# robot.net
KiCad netlist of a schematic drawn in EAGLE
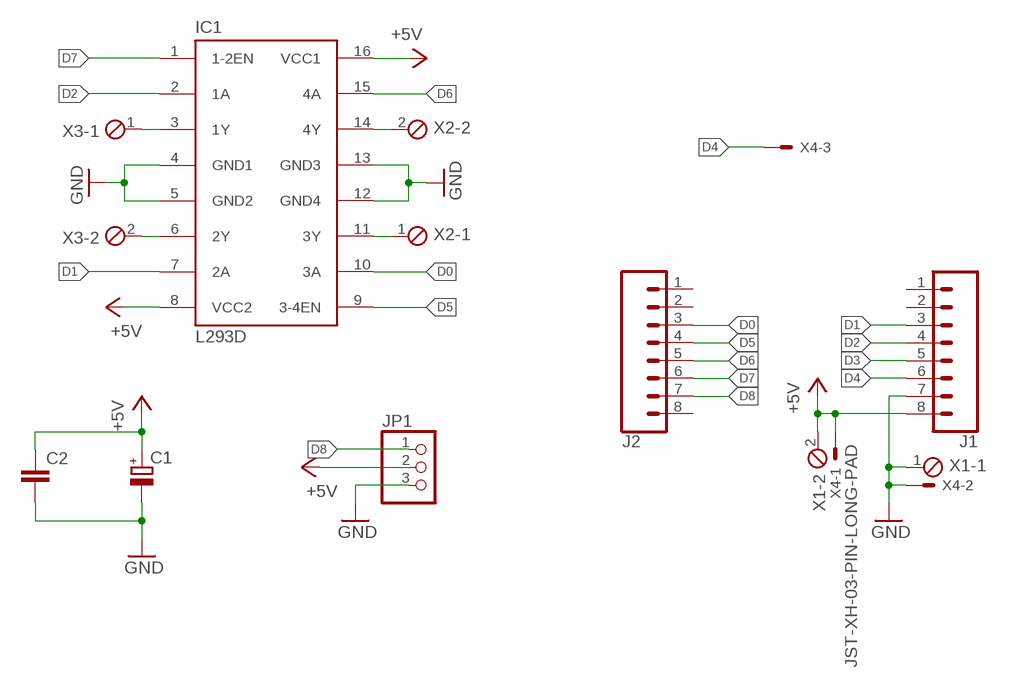
[diagram p0: schematic, sheet 1]

(export (version "E")
  (design (tool "Eeschema 10.0.6"))
  (components
    (comp (ref "C1")
      (value "CPOL-EUE2.5-7")
      (footprint "eagle-import:E2,5-7")
      (libsource (lib "eagle-import") (part "CPOL-EUE2.5-7"))
    )
    (comp (ref "C2")
      (value "C-EUC0805K")
      (footprint "eagle-import:C0805K")
      (libsource (lib "eagle-import") (part "C-EUC0805K"))
    )
    (comp (ref "IC1")
      (value "L293D")
      (footprint "eagle-import:DIL16")
      (libsource (lib "eagle-import") (part "L293D"))
    )
    (comp (ref "J1")
      (value "CONN_08\"")
      (footprint "eagle-import:1X08")
      (libsource (lib "eagle-import") (part "CONN_08{dblquote}"))
    )
    (comp (ref "J2")
      (value "CONN_08\"")
      (footprint "eagle-import:1X08")
      (libsource (lib "eagle-import") (part "CONN_08{dblquote}"))
    )
    (comp (ref "JP1")
      (value "PINHD-1X3")
      (footprint "eagle-import:1X03")
      (libsource (lib "eagle-import") (part "PINHD-1X3"))
    )
    (comp (ref "X1")
      (value "MPT2")
      (footprint "eagle-import:2POL254")
      (libsource (lib "eagle-import") (part "MPT2"))
    )
    (comp (ref "X2")
      (value "MPT2")
      (footprint "eagle-import:2POL254")
      (libsource (lib "eagle-import") (part "MPT2"))
    )
    (comp (ref "X3")
      (value "MPT2")
      (footprint "eagle-import:2POL254")
      (libsource (lib "eagle-import") (part "MPT2"))
    )
    (comp (ref "X4")
      (value "JST-XH-03-PIN-LONG-PAD")
      (footprint "eagle-import:JST-XH-03-PACKAGE-LONG-PAD")
      (libsource (lib "eagle-import") (part "JST-XH-03-PIN-LONG-PAD"))
    )
  )
  (nets
    (net (code "1") (name "+5V") (class "Default")
      (node (ref "C1") (pin "+") (pinfunction "+_+") (pintype "passive"))
      (node (ref "C2") (pin "1") (pinfunction "1_1") (pintype "passive"))
      (node (ref "IC1") (pin "16") (pinfunction "VCC1_16") (pintype "power_in"))
      (node (ref "IC1") (pin "8") (pinfunction "VCC2_8") (pintype "power_in"))
      (node (ref "J1") (pin "8") (pinfunction "8_8") (pintype "passive"))
      (node (ref "JP1") (pin "2") (pinfunction "2_2") (pintype "passive"))
      (node (ref "X1") (pin "2") (pinfunction "1_2") (pintype "passive"))
      (node (ref "X4") (pin "1") (pinfunction "S_1") (pintype "passive"))
    )
    (net (code "2") (name "D0") (class "Default")
      (node (ref "IC1") (pin "10") (pinfunction "3A_10") (pintype "input"))
      (node (ref "J2") (pin "3") (pinfunction "3_3") (pintype "passive"))
    )
    (net (code "3") (name "D1") (class "Default")
      (node (ref "IC1") (pin "7") (pinfunction "2A_7") (pintype "input"))
      (node (ref "J1") (pin "3") (pinfunction "3_3") (pintype "passive"))
    )
    (net (code "4") (name "D2") (class "Default")
      (node (ref "IC1") (pin "2") (pinfunction "1A_2") (pintype "input"))
      (node (ref "J1") (pin "4") (pinfunction "4_4") (pintype "passive"))
    )
    (net (code "5") (name "D3") (class "Default")
      (node (ref "J1") (pin "5") (pinfunction "5_5") (pintype "passive"))
    )
    (net (code "6") (name "D4") (class "Default")
      (node (ref "J1") (pin "6") (pinfunction "6_6") (pintype "passive"))
      (node (ref "X4") (pin "3") (pinfunction "S_3") (pintype "passive"))
    )
    (net (code "7") (name "D5") (class "Default")
      (node (ref "IC1") (pin "9") (pinfunction "3-4EN_9") (pintype "input"))
      (node (ref "J2") (pin "4") (pinfunction "4_4") (pintype "passive"))
    )
    (net (code "8") (name "D6") (class "Default")
      (node (ref "IC1") (pin "15") (pinfunction "4A_15") (pintype "input"))
      (node (ref "J2") (pin "5") (pinfunction "5_5") (pintype "passive"))
    )
    (net (code "9") (name "D7") (class "Default")
      (node (ref "IC1") (pin "1") (pinfunction "1-2EN_1") (pintype "input"))
      (node (ref "J2") (pin "6") (pinfunction "6_6") (pintype "passive"))
    )
    (net (code "10") (name "D8") (class "Default")
      (node (ref "J2") (pin "7") (pinfunction "7_7") (pintype "passive"))
      (node (ref "JP1") (pin "1") (pinfunction "1_1") (pintype "passive"))
    )
    (net (code "11") (name "GND") (class "Default")
      (node (ref "C1") (pin "-") (pinfunction "-_-") (pintype "passive"))
      (node (ref "C2") (pin "2") (pinfunction "2_2") (pintype "passive"))
      (node (ref "IC1") (pin "12") (pinfunction "GND4_12") (pintype "power_in"))
      (node (ref "IC1") (pin "13") (pinfunction "GND3_13") (pintype "power_in"))
      (node (ref "IC1") (pin "4") (pinfunction "GND1_4") (pintype "power_in"))
      (node (ref "IC1") (pin "5") (pinfunction "GND2_5") (pintype "power_in"))
      (node (ref "J1") (pin "7") (pinfunction "7_7") (pintype "passive"))
      (node (ref "JP1") (pin "3") (pinfunction "3_3") (pintype "passive"))
      (node (ref "X1") (pin "1") (pinfunction "1_1") (pintype "passive"))
      (node (ref "X4") (pin "2") (pinfunction "S_2") (pintype "passive"))
    )
    (net (code "12") (name "Net-(IC1-1Y)") (class "Default")
      (node (ref "IC1") (pin "3") (pinfunction "1Y_3") (pintype "output"))
      (node (ref "X3") (pin "1") (pinfunction "1_1") (pintype "passive"))
    )
    (net (code "13") (name "Net-(IC1-2Y)") (class "Default")
      (node (ref "IC1") (pin "6") (pinfunction "2Y_6") (pintype "output"))
      (node (ref "X3") (pin "2") (pinfunction "1_2") (pintype "passive"))
    )
    (net (code "14") (name "Net-(IC1-3Y)") (class "Default")
      (node (ref "IC1") (pin "11") (pinfunction "3Y_11") (pintype "output"))
      (node (ref "X2") (pin "1") (pinfunction "1_1") (pintype "passive"))
    )
    (net (code "15") (name "Net-(IC1-4Y)") (class "Default")
      (node (ref "IC1") (pin "14") (pinfunction "4Y_14") (pintype "output"))
      (node (ref "X2") (pin "2") (pinfunction "1_2") (pintype "passive"))
    )
    (net (code "16") (name "unconnected-(J1-Pad1)") (class "Default")
      (node (ref "J1") (pin "1") (pinfunction "1_1") (pintype "passive"))
    )
    (net (code "17") (name "unconnected-(J1-Pad2)") (class "Default")
      (node (ref "J1") (pin "2") (pinfunction "2_2") (pintype "passive"))
    )
    (net (code "18") (name "unconnected-(J2-Pad1)") (class "Default")
      (node (ref "J2") (pin "1") (pinfunction "1_1") (pintype "passive"))
    )
    (net (code "19") (name "unconnected-(J2-Pad2)") (class "Default")
      (node (ref "J2") (pin "2") (pinfunction "2_2") (pintype "passive"))
    )
    (net (code "20") (name "unconnected-(J2-Pad8)") (class "Default")
      (node (ref "J2") (pin "8") (pinfunction "8_8") (pintype "passive"))
    )
  )
)
